# Chassis_Board_V2.net
KiCad netlist of a schematic drawn in EAGLE
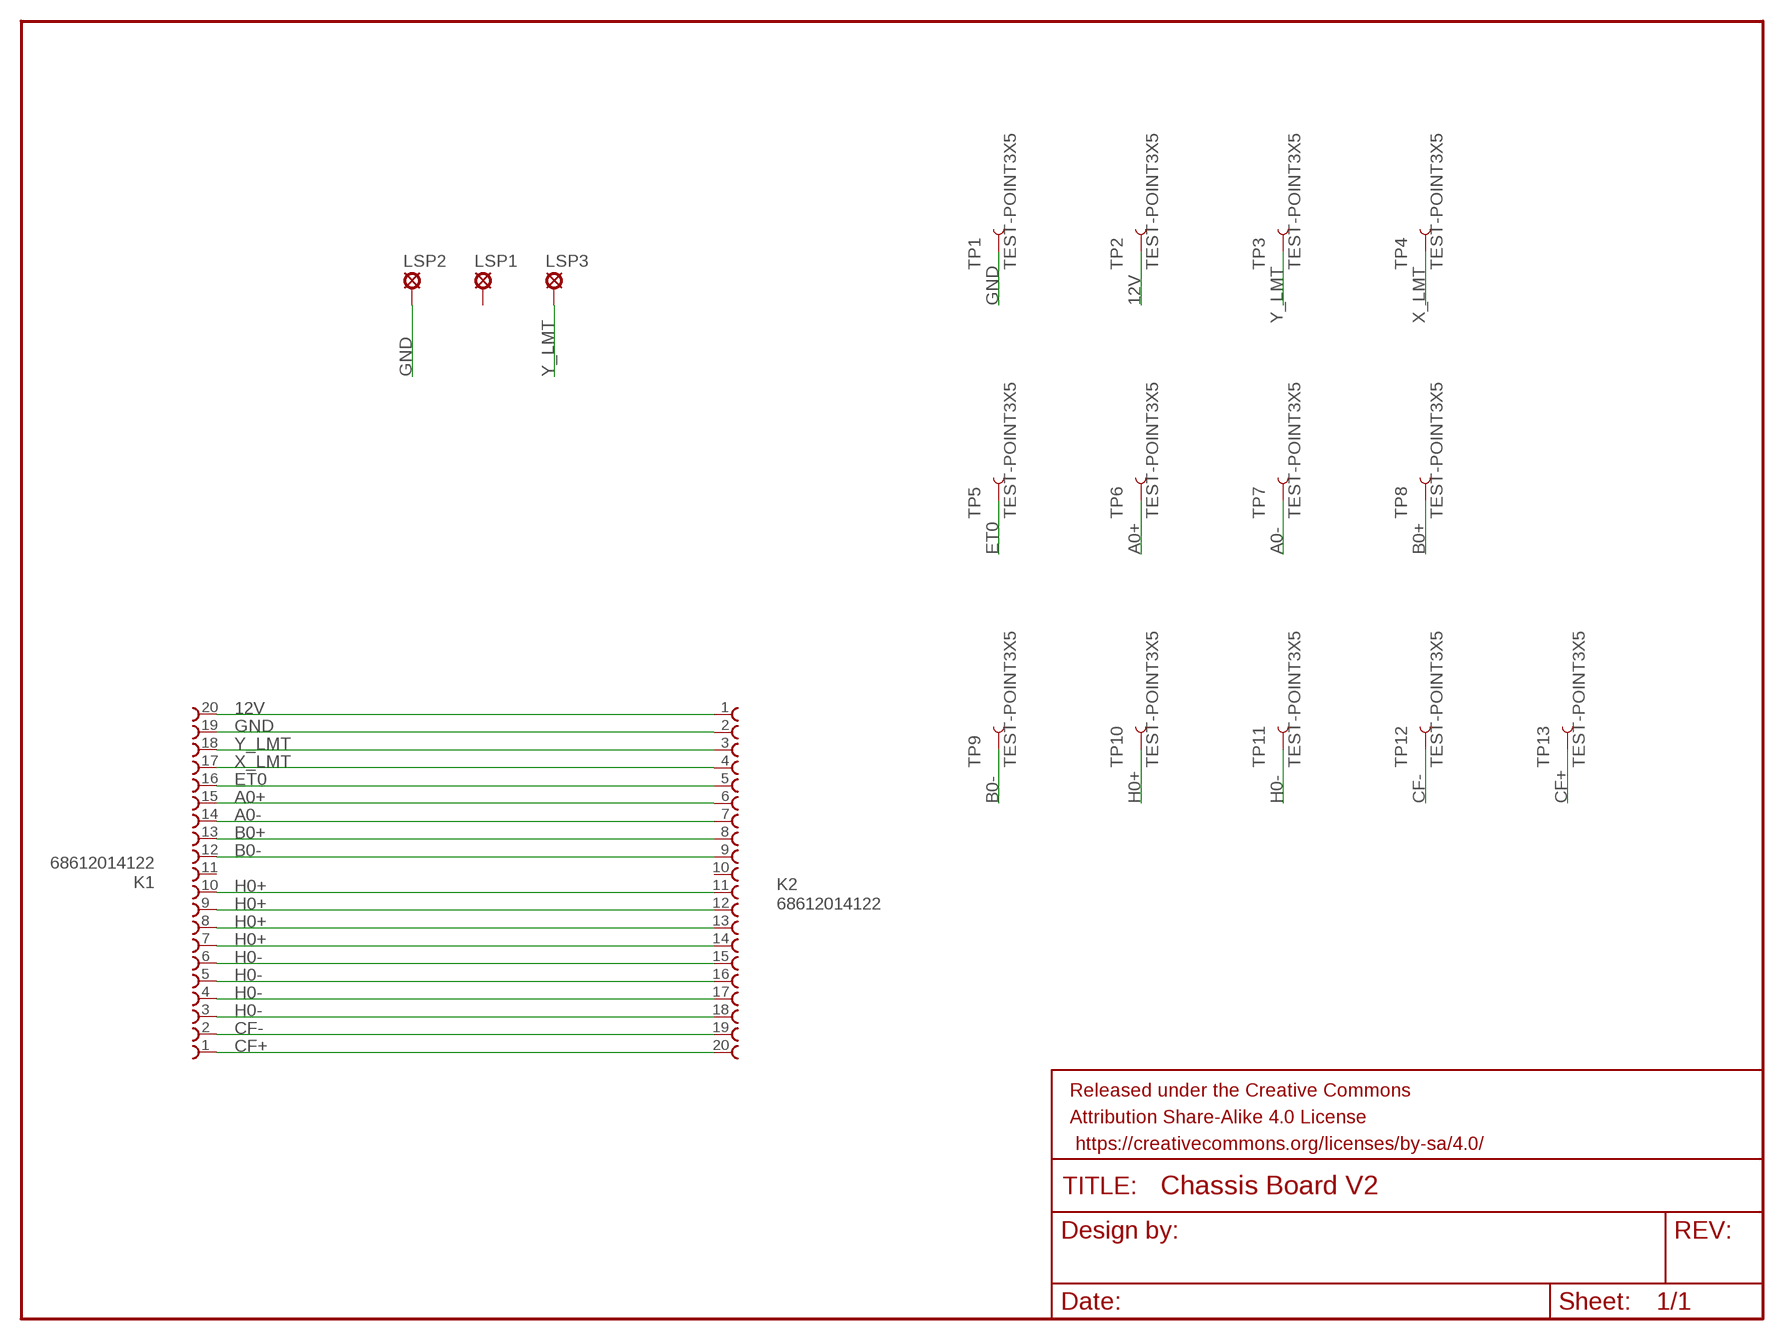
[diagram p0: schematic, sheet 1]

(export (version "E")
  (design (tool "Eeschema 10.0.6"))
  (components
    (comp (ref "FRAME1")
      (value "FRAME-LETTER")
      (footprint "eagle-import:CREATIVE_COMMONS")
      (libsource (lib "eagle-import") (part "FRAME-LETTER"))
    )
    (comp (ref "K1")
      (value "68612014122")
      (footprint "eagle-import:68612014122")
      (libsource (lib "eagle-import") (part "68612014122"))
    )
    (comp (ref "K2")
      (value "68612014122")
      (footprint "eagle-import:68612014122")
      (libsource (lib "eagle-import") (part "68612014122"))
    )
    (comp (ref "LSP1")
      (value "NO")
      (footprint "eagle-import:LSP13")
      (libsource (lib "eagle-import") (part "LSP13"))
    )
    (comp (ref "LSP2")
      (value "NC")
      (footprint "eagle-import:LSP13")
      (libsource (lib "eagle-import") (part "LSP13"))
    )
    (comp (ref "LSP3")
      (value "C")
      (footprint "eagle-import:LSP13")
      (libsource (lib "eagle-import") (part "LSP13"))
    )
    (comp (ref "TP1")
      (value "TEST-POINT3X5")
      (footprint "eagle-import:PAD.03X.05")
      (libsource (lib "eagle-import") (part "TEST-POINT3X5"))
    )
    (comp (ref "TP2")
      (value "TEST-POINT3X5")
      (footprint "eagle-import:PAD.03X.05")
      (libsource (lib "eagle-import") (part "TEST-POINT3X5"))
    )
    (comp (ref "TP3")
      (value "TEST-POINT3X5")
      (footprint "eagle-import:PAD.03X.05")
      (libsource (lib "eagle-import") (part "TEST-POINT3X5"))
    )
    (comp (ref "TP4")
      (value "TEST-POINT3X5")
      (footprint "eagle-import:PAD.03X.05")
      (libsource (lib "eagle-import") (part "TEST-POINT3X5"))
    )
    (comp (ref "TP5")
      (value "TEST-POINT3X5")
      (footprint "eagle-import:PAD.03X.05")
      (libsource (lib "eagle-import") (part "TEST-POINT3X5"))
    )
    (comp (ref "TP6")
      (value "TEST-POINT3X5")
      (footprint "eagle-import:PAD.03X.05")
      (libsource (lib "eagle-import") (part "TEST-POINT3X5"))
    )
    (comp (ref "TP7")
      (value "TEST-POINT3X5")
      (footprint "eagle-import:PAD.03X.05")
      (libsource (lib "eagle-import") (part "TEST-POINT3X5"))
    )
    (comp (ref "TP8")
      (value "TEST-POINT3X5")
      (footprint "eagle-import:PAD.03X.05")
      (libsource (lib "eagle-import") (part "TEST-POINT3X5"))
    )
    (comp (ref "TP9")
      (value "TEST-POINT3X5")
      (footprint "eagle-import:PAD.03X.05")
      (libsource (lib "eagle-import") (part "TEST-POINT3X5"))
    )
    (comp (ref "TP10")
      (value "TEST-POINT3X5")
      (footprint "eagle-import:PAD.03X.05")
      (libsource (lib "eagle-import") (part "TEST-POINT3X5"))
    )
    (comp (ref "TP11")
      (value "TEST-POINT3X5")
      (footprint "eagle-import:PAD.03X.05")
      (libsource (lib "eagle-import") (part "TEST-POINT3X5"))
    )
    (comp (ref "TP12")
      (value "TEST-POINT3X5")
      (footprint "eagle-import:PAD.03X.05")
      (libsource (lib "eagle-import") (part "TEST-POINT3X5"))
    )
    (comp (ref "TP13")
      (value "TEST-POINT3X5")
      (footprint "eagle-import:PAD.03X.05")
      (libsource (lib "eagle-import") (part "TEST-POINT3X5"))
    )
  )
  (nets
    (net (code "1") (name "/12V") (class "Default")
      (node (ref "K1") (pin "20") (pinfunction "20_20") (pintype "passive"))
      (node (ref "K2") (pin "1") (pinfunction "1_1") (pintype "passive"))
      (node (ref "TP2") (pin "P$1") (pinfunction "1_P$1") (pintype "bidirectional"))
    )
    (net (code "2") (name "/A0+") (class "Default")
      (node (ref "K1") (pin "15") (pinfunction "15_15") (pintype "passive"))
      (node (ref "K2") (pin "6") (pinfunction "6_6") (pintype "passive"))
      (node (ref "TP6") (pin "P$1") (pinfunction "1_P$1") (pintype "bidirectional"))
    )
    (net (code "3") (name "/A0-") (class "Default")
      (node (ref "K1") (pin "14") (pinfunction "14_14") (pintype "passive"))
      (node (ref "K2") (pin "7") (pinfunction "7_7") (pintype "passive"))
      (node (ref "TP7") (pin "P$1") (pinfunction "1_P$1") (pintype "bidirectional"))
    )
    (net (code "4") (name "/B0+") (class "Default")
      (node (ref "K1") (pin "13") (pinfunction "13_13") (pintype "passive"))
      (node (ref "K2") (pin "8") (pinfunction "8_8") (pintype "passive"))
      (node (ref "TP8") (pin "P$1") (pinfunction "1_P$1") (pintype "bidirectional"))
    )
    (net (code "5") (name "/B0-") (class "Default")
      (node (ref "K1") (pin "12") (pinfunction "12_12") (pintype "passive"))
      (node (ref "K2") (pin "9") (pinfunction "9_9") (pintype "passive"))
      (node (ref "TP9") (pin "P$1") (pinfunction "1_P$1") (pintype "bidirectional"))
    )
    (net (code "6") (name "/CF+") (class "Default")
      (node (ref "K1") (pin "1") (pinfunction "1_1") (pintype "passive"))
      (node (ref "K2") (pin "20") (pinfunction "20_20") (pintype "passive"))
      (node (ref "TP13") (pin "P$1") (pinfunction "1_P$1") (pintype "bidirectional"))
    )
    (net (code "7") (name "/CF-") (class "Default")
      (node (ref "K1") (pin "2") (pinfunction "2_2") (pintype "passive"))
      (node (ref "K2") (pin "19") (pinfunction "19_19") (pintype "passive"))
      (node (ref "TP12") (pin "P$1") (pinfunction "1_P$1") (pintype "bidirectional"))
    )
    (net (code "8") (name "/ET0") (class "Default")
      (node (ref "K1") (pin "16") (pinfunction "16_16") (pintype "passive"))
      (node (ref "K2") (pin "5") (pinfunction "5_5") (pintype "passive"))
      (node (ref "TP5") (pin "P$1") (pinfunction "1_P$1") (pintype "bidirectional"))
    )
    (net (code "9") (name "/GND") (class "Default")
      (node (ref "K1") (pin "19") (pinfunction "19_19") (pintype "passive"))
      (node (ref "K2") (pin "2") (pinfunction "2_2") (pintype "passive"))
      (node (ref "LSP2") (pin "MP") (pinfunction "MP_MP") (pintype "passive"))
      (node (ref "TP1") (pin "P$1") (pinfunction "1_P$1") (pintype "bidirectional"))
    )
    (net (code "10") (name "/H0+") (class "Default")
      (node (ref "K1") (pin "10") (pinfunction "10_10") (pintype "passive"))
      (node (ref "K1") (pin "7") (pinfunction "7_7") (pintype "passive"))
      (node (ref "K1") (pin "8") (pinfunction "8_8") (pintype "passive"))
      (node (ref "K1") (pin "9") (pinfunction "9_9") (pintype "passive"))
      (node (ref "K2") (pin "11") (pinfunction "11_11") (pintype "passive"))
      (node (ref "K2") (pin "12") (pinfunction "12_12") (pintype "passive"))
      (node (ref "K2") (pin "13") (pinfunction "13_13") (pintype "passive"))
      (node (ref "K2") (pin "14") (pinfunction "14_14") (pintype "passive"))
      (node (ref "TP10") (pin "P$1") (pinfunction "1_P$1") (pintype "bidirectional"))
    )
    (net (code "11") (name "/H0-") (class "Default")
      (node (ref "K1") (pin "3") (pinfunction "3_3") (pintype "passive"))
      (node (ref "K1") (pin "4") (pinfunction "4_4") (pintype "passive"))
      (node (ref "K1") (pin "5") (pinfunction "5_5") (pintype "passive"))
      (node (ref "K1") (pin "6") (pinfunction "6_6") (pintype "passive"))
      (node (ref "K2") (pin "15") (pinfunction "15_15") (pintype "passive"))
      (node (ref "K2") (pin "16") (pinfunction "16_16") (pintype "passive"))
      (node (ref "K2") (pin "17") (pinfunction "17_17") (pintype "passive"))
      (node (ref "K2") (pin "18") (pinfunction "18_18") (pintype "passive"))
      (node (ref "TP11") (pin "P$1") (pinfunction "1_P$1") (pintype "bidirectional"))
    )
    (net (code "12") (name "/X_LMT") (class "Default")
      (node (ref "K1") (pin "17") (pinfunction "17_17") (pintype "passive"))
      (node (ref "K2") (pin "4") (pinfunction "4_4") (pintype "passive"))
      (node (ref "TP4") (pin "P$1") (pinfunction "1_P$1") (pintype "bidirectional"))
    )
    (net (code "13") (name "/Y_LMT") (class "Default")
      (node (ref "K1") (pin "18") (pinfunction "18_18") (pintype "passive"))
      (node (ref "K2") (pin "3") (pinfunction "3_3") (pintype "passive"))
      (node (ref "LSP3") (pin "MP") (pinfunction "MP_MP") (pintype "passive"))
      (node (ref "TP3") (pin "P$1") (pinfunction "1_P$1") (pintype "bidirectional"))
    )
    (net (code "14") (name "unconnected-(K1-Pad11)") (class "Default")
      (node (ref "K1") (pin "11") (pinfunction "11_11") (pintype "passive"))
    )
    (net (code "15") (name "unconnected-(K2-Pad10)") (class "Default")
      (node (ref "K2") (pin "10") (pinfunction "10_10") (pintype "passive"))
    )
    (net (code "16") (name "unconnected-(LSP1-PadMP)") (class "Default")
      (node (ref "LSP1") (pin "MP") (pinfunction "MP_MP") (pintype "passive"))
    )
  )
)
